# Battery_Management.net
KiCad netlist of a schematic drawn in Altium Designer
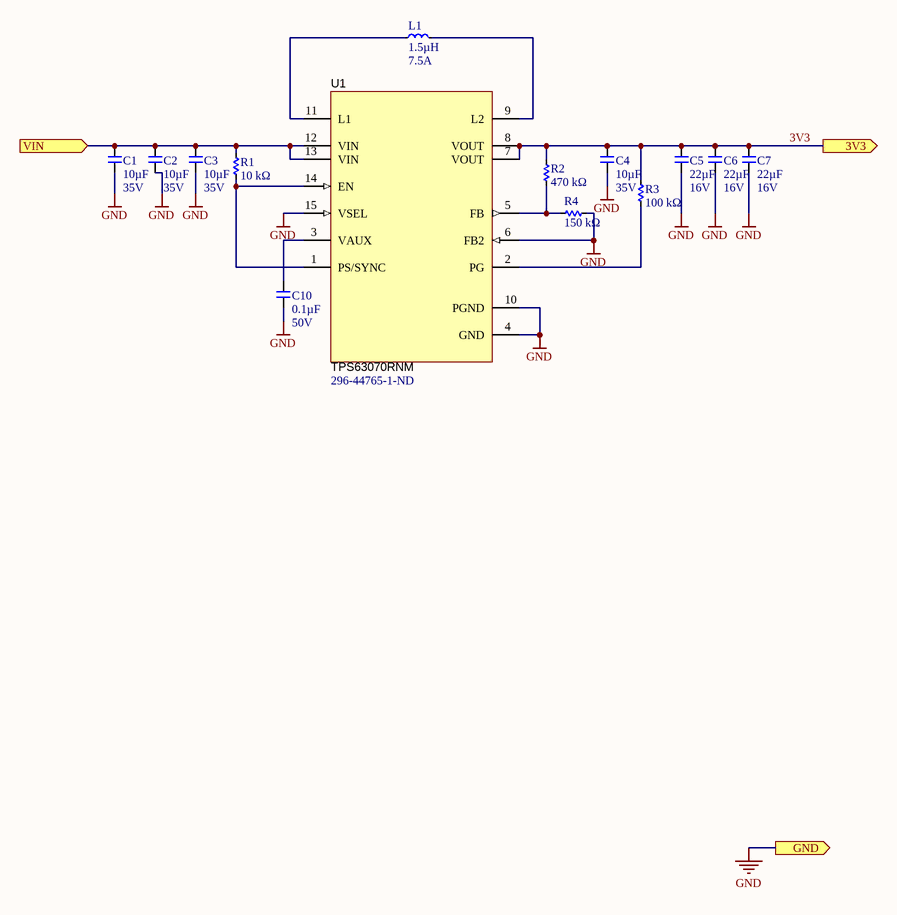
[diagram p0: Battery_Management.SchDoc]

(export (version "E")
  (design (tool "Eeschema 10.0.6"))
  (components
    (comp (ref "C1")
      (value "__template_cap")
      (footprint "C0603")
      (fields
        (field (name "CAPACITANCE (SHORTHAND)") "10µF")
        (field (name "RATED VOLTAGE") "35V")
        (field (name "MANUFACTURER") "Murata Electronics North America")
      )
      (libsource (lib "passives") (part "__template_cap"))
    )
    (comp (ref "C2")
      (value "__template_cap")
      (footprint "C0603")
      (fields
        (field (name "CAPACITANCE (SHORTHAND)") "10µF")
        (field (name "RATED VOLTAGE") "35V")
        (field (name "MANUFACTURER") "Murata Electronics North America")
      )
      (libsource (lib "passives") (part "__template_cap"))
    )
    (comp (ref "C3")
      (value "__template_cap")
      (footprint "C0603")
      (fields
        (field (name "CAPACITANCE (SHORTHAND)") "10µF")
        (field (name "RATED VOLTAGE") "35V")
        (field (name "MANUFACTURER") "Murata Electronics North America")
      )
      (libsource (lib "passives") (part "__template_cap"))
    )
    (comp (ref "C4")
      (value "__template_cap")
      (footprint "C0603")
      (fields
        (field (name "CAPACITANCE (SHORTHAND)") "10µF")
        (field (name "RATED VOLTAGE") "35V")
        (field (name "MANUFACTURER") "Murata Electronics North America")
      )
      (libsource (lib "passives") (part "__template_cap"))
    )
    (comp (ref "C5")
      (value "__template_cap")
      (footprint "C0603")
      (fields
        (field (name "CAPACITANCE (SHORTHAND)") "22µF")
        (field (name "RATED VOLTAGE") "16V")
        (field (name "MANUFACTURER") "Samsung Electro-Mechanics")
      )
      (libsource (lib "passives") (part "__template_cap"))
    )
    (comp (ref "C6")
      (value "__template_cap")
      (footprint "C0603")
      (fields
        (field (name "CAPACITANCE (SHORTHAND)") "22µF")
        (field (name "RATED VOLTAGE") "16V")
        (field (name "MANUFACTURER") "Samsung Electro-Mechanics")
      )
      (libsource (lib "passives") (part "__template_cap"))
    )
    (comp (ref "C7")
      (value "__template_cap")
      (footprint "C0603")
      (fields
        (field (name "CAPACITANCE (SHORTHAND)") "22µF")
        (field (name "RATED VOLTAGE") "16V")
        (field (name "MANUFACTURER") "Samsung Electro-Mechanics")
      )
      (libsource (lib "passives") (part "__template_cap"))
    )
    (comp (ref "C10")
      (value "__template_cap")
      (footprint "C0603")
      (fields
        (field (name "CAPACITANCE (SHORTHAND)") "0.1µF")
        (field (name "RATED VOLTAGE") "50V")
        (field (name "MANUFACTURER") "Murata Electronics North America")
      )
      (libsource (lib "passives") (part "__template_cap"))
    )
    (comp (ref "L1")
      (value "IND_IHLP2020CZER1R5M11")
      (footprint "SMD5230")
      (description "INDUCTOR POWER 1.5UH 7.5A SMD")
      (fields
        (field (name "MANUFACTURER") "Vishay Dale")
        (field (name "MANUFACTURER PART NUMBER") "IHLP2020CZER1R5M11")
        (field (name "INDUCTANCE") "1.5µH")
        (field (name "CURRENT RATING") "7.5A")
      )
      (libsource (lib "SSI") (part "IND_IHLP2020CZER1R5M11"))
    )
    (comp (ref "R1")
      (value "__template_resistor")
      (footprint "R0603")
      (fields
        (field (name "RESISTANCE") "10 kΩ")
        (field (name "MANUFACTURER PART NUMBER") "RC0603FR-0710KL")
        (field (name "MANUFACTURER") "Yageo")
        (field (name "TOLERANCE") "±1%")
      )
      (libsource (lib "passives") (part "__template_resistor"))
    )
    (comp (ref "R2")
      (value "RC0603FR-07470KL")
      (footprint "R0603")
      (fields
        (field (name "MANUFACTURER") "Yageo")
        (field (name "TOLERANCE") "±1%")
        (field (name "RESISTANCE") "470 kΩ")
      )
      (libsource (lib "passives") (part "__template_resistor"))
    )
    (comp (ref "R3")
      (value "RC0603FR-07100KL")
      (footprint "R0603")
      (fields
        (field (name "MANUFACTURER") "Yageo")
        (field (name "TOLERANCE") "±1%")
        (field (name "RESISTANCE") "100 kΩ")
      )
      (libsource (lib "passives") (part "__template_resistor"))
    )
    (comp (ref "R4")
      (value "RC0603FR-07150KL")
      (footprint "R0603")
      (fields
        (field (name "MANUFACTURER") "Yageo")
        (field (name "TOLERANCE") "±1%")
        (field (name "RESISTANCE") "150 kΩ")
      )
      (libsource (lib "passives") (part "__template_resistor"))
    )
    (comp (ref "U1")
      (value "TPS63070RNM")
      (footprint "TPS63070")
      (description "BUCKBOOST TPS63070RNM, RNM0015A")
      (fields
        (field (name "MANUFACTURER") "Texas Instruments")
        (field (name "SUPPLIER PART NUMBER 1") "296-44765-1-ND")
        (field (name "SYMBOLCREATOR") "Altium")
        (field (name "PUBLISHER") "Texas Instruments")
      )
      (libsource (lib "SSI") (part "TPS63070RNM"))
    )
  )
  (nets
    (net (code "1") (name "/3V3") (class "Default")
      (node (ref "C4") (pin "1") (pintype "passive"))
      (node (ref "C5") (pin "1") (pintype "passive"))
      (node (ref "C6") (pin "1") (pintype "passive"))
      (node (ref "C7") (pin "1") (pintype "passive"))
      (node (ref "R2") (pin "2") (pintype "passive"))
      (node (ref "R3") (pin "2") (pintype "passive"))
      (node (ref "U1") (pin "7") (pinfunction "VOUT_7") (pintype "power_in"))
      (node (ref "U1") (pin "8") (pinfunction "VOUT_8") (pintype "power_in"))
    )
    (net (code "2") (name "/VIN") (class "Default")
      (node (ref "C1") (pin "1") (pintype "passive"))
      (node (ref "C2") (pin "1") (pintype "passive"))
      (node (ref "C3") (pin "1") (pintype "passive"))
      (node (ref "R1") (pin "2") (pintype "passive"))
      (node (ref "U1") (pin "12") (pinfunction "VIN_12") (pintype "power_in"))
      (node (ref "U1") (pin "13") (pinfunction "VIN_13") (pintype "power_in"))
    )
    (net (code "3") (name "GND") (class "Default")
      (node (ref "C1") (pin "2") (pintype "passive"))
      (node (ref "C10") (pin "2") (pintype "passive"))
      (node (ref "C2") (pin "2") (pintype "passive"))
      (node (ref "C3") (pin "2") (pintype "passive"))
      (node (ref "C4") (pin "2") (pintype "passive"))
      (node (ref "C5") (pin "2") (pintype "passive"))
      (node (ref "C6") (pin "2") (pintype "passive"))
      (node (ref "C7") (pin "2") (pintype "passive"))
      (node (ref "R4") (pin "2") (pintype "passive"))
      (node (ref "U1") (pin "10") (pinfunction "PGND_10") (pintype "power_in"))
      (node (ref "U1") (pin "15") (pinfunction "VSEL_15") (pintype "input"))
      (node (ref "U1") (pin "4") (pinfunction "GND_4") (pintype "power_in"))
      (node (ref "U1") (pin "6") (pinfunction "FB2_6") (pintype "input"))
    )
    (net (code "4") (name "Net-(U1-EN)") (class "Default")
      (node (ref "R1") (pin "1") (pintype "passive"))
      (node (ref "U1") (pin "1") (pinfunction "PS/SYNC_1") (pintype "passive"))
      (node (ref "U1") (pin "14") (pinfunction "EN_14") (pintype "input"))
    )
    (net (code "5") (name "Net-(U1-FB)") (class "Default")
      (node (ref "R2") (pin "1") (pintype "passive"))
      (node (ref "R4") (pin "1") (pintype "passive"))
      (node (ref "U1") (pin "5") (pinfunction "FB_5") (pintype "output"))
    )
    (net (code "6") (name "Net-(U1-L1)") (class "Default")
      (node (ref "L1") (pin "1") (pintype "passive"))
      (node (ref "U1") (pin "11") (pinfunction "L1_11") (pintype "passive"))
    )
    (net (code "7") (name "Net-(U1-L2)") (class "Default")
      (node (ref "L1") (pin "2") (pintype "passive"))
      (node (ref "U1") (pin "9") (pinfunction "L2_9") (pintype "passive"))
    )
    (net (code "8") (name "Net-(U1-PG)") (class "Default")
      (node (ref "R3") (pin "1") (pintype "passive"))
      (node (ref "U1") (pin "2") (pinfunction "PG_2") (pintype "open_collector"))
    )
    (net (code "9") (name "Net-(U1-VAUX)") (class "Default")
      (node (ref "C10") (pin "1") (pintype "passive"))
      (node (ref "U1") (pin "3") (pinfunction "VAUX_3") (pintype "passive"))
    )
  )
)
